# EEPROM_Programmer.net
KiCad netlist of a schematic drawn in EAGLE
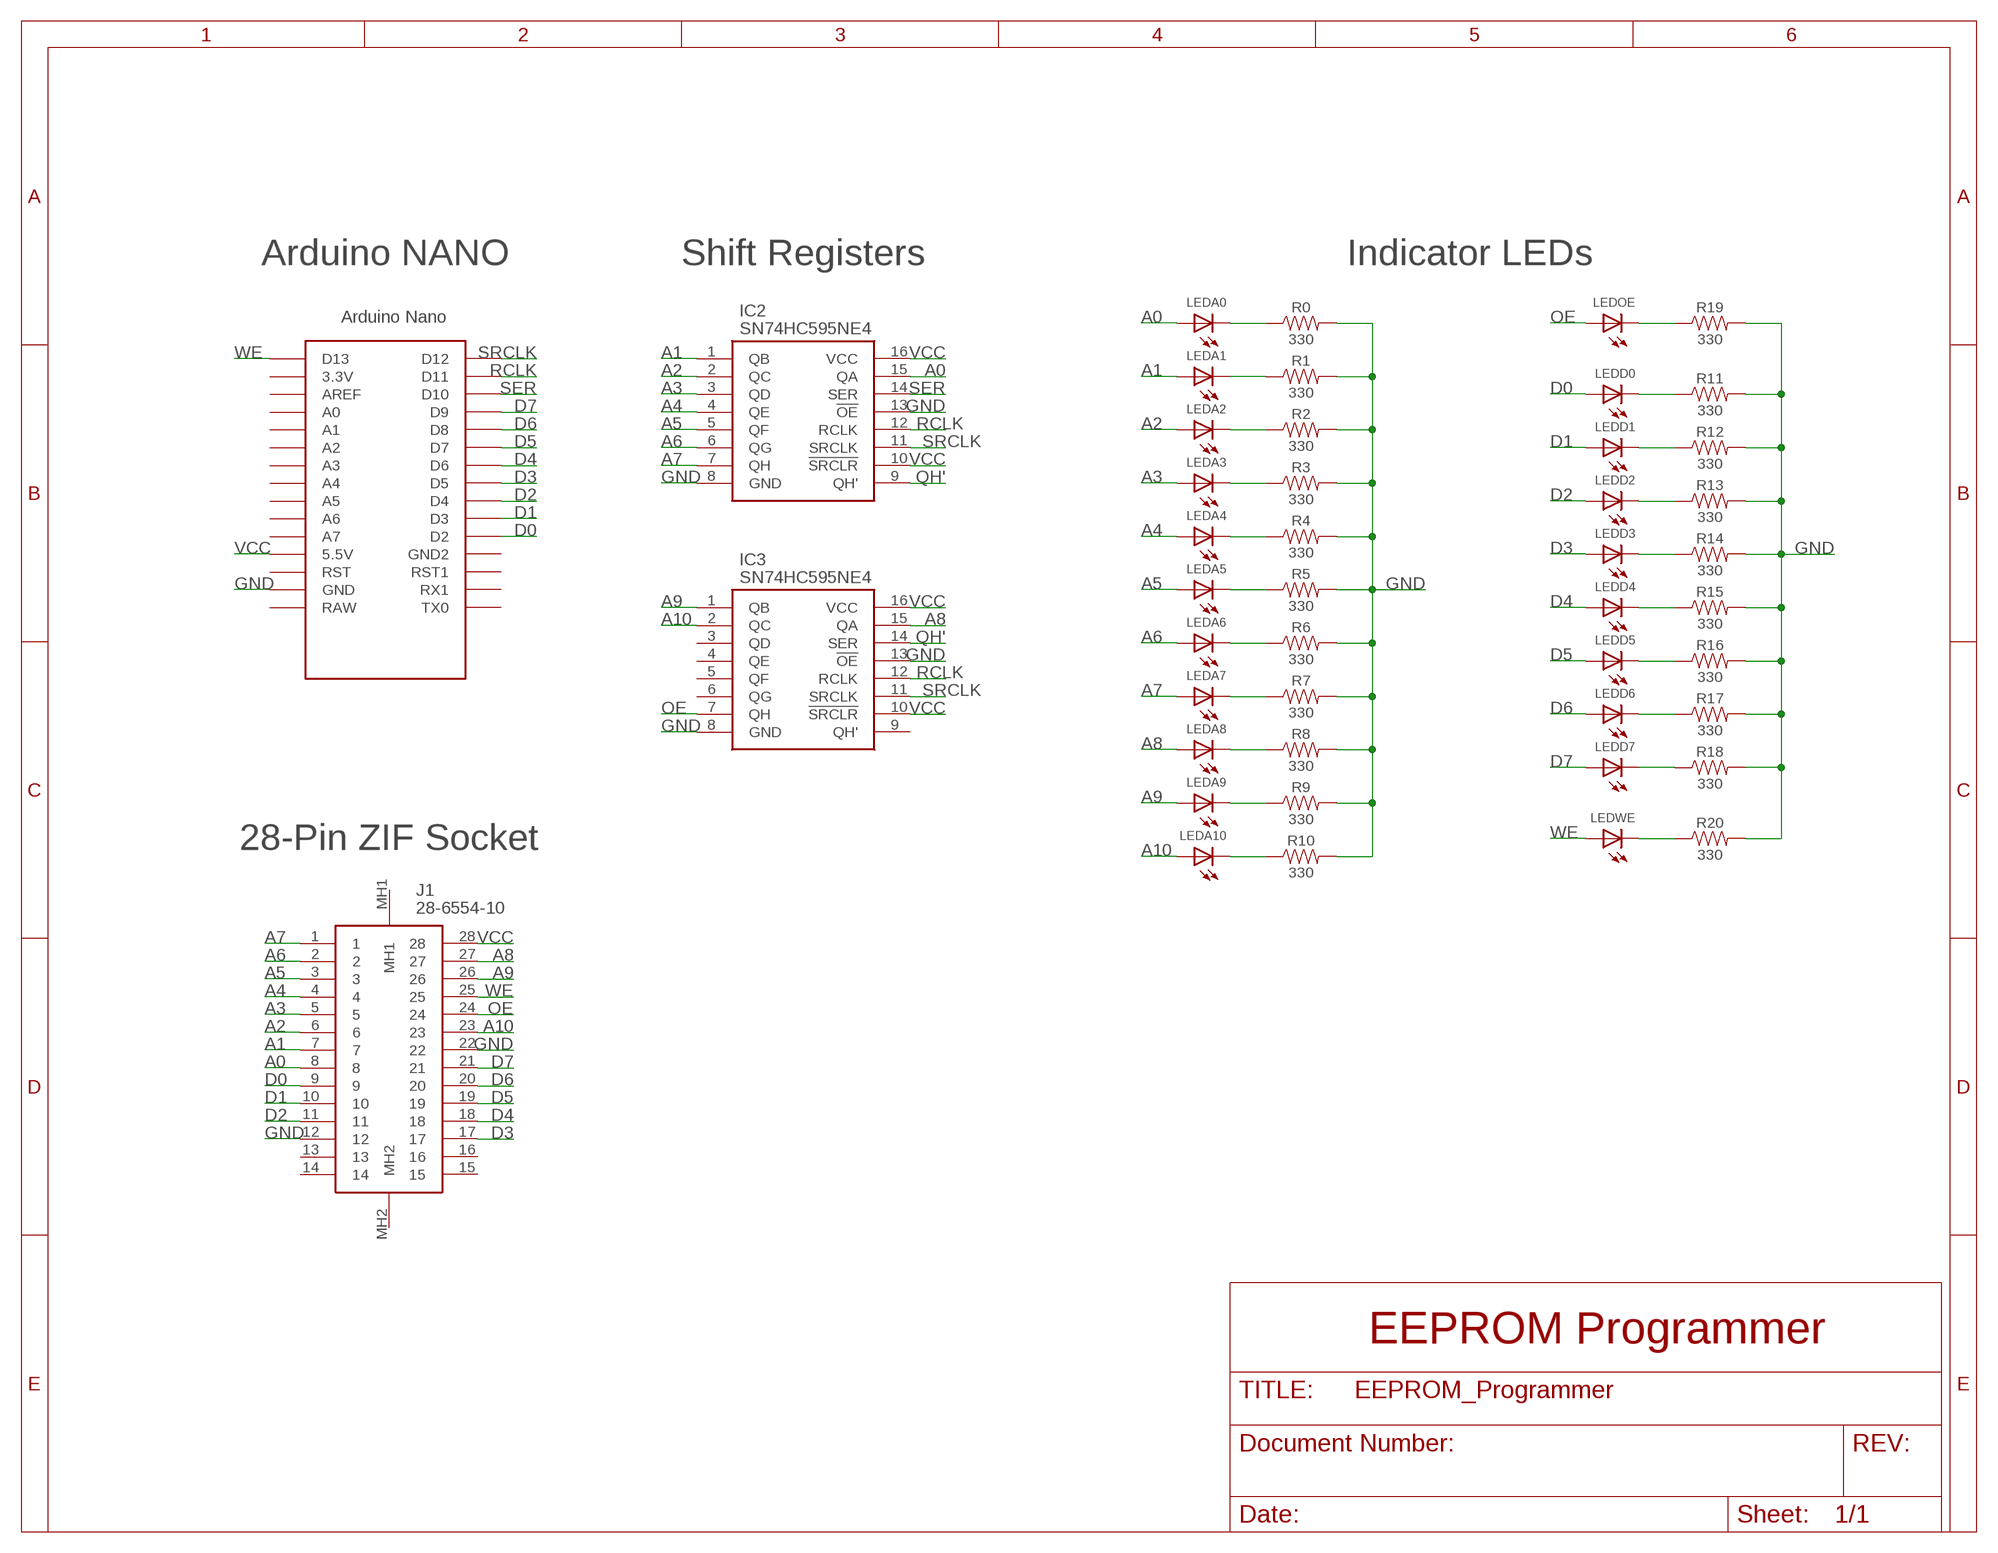
[diagram p0: schematic, sheet 1]

(export (version "E")
  (design (tool "Eeschema 10.0.6"))
  (components
    (comp (ref "IC2")
      (value "SN74HC595NE4")
      (footprint "eagle-import:DIP794W53P254L1930H508Q16N")
      (fields (field (name "MOUSER_PART_NUMBER") "595-SN74HC595NE4"))
      (libsource (lib "eagle-import") (part "SN74HC595NE4"))
    )
    (comp (ref "IC3")
      (value "SN74HC595NE4")
      (footprint "eagle-import:DIP794W53P254L1930H508Q16N")
      (fields (field (name "MOUSER_PART_NUMBER") "595-SN74HC595NE4"))
      (libsource (lib "eagle-import") (part "SN74HC595NE4"))
    )
    (comp (ref "J1")
      (value "28-6554-10")
      (footprint "eagle-import:28655410")
      (fields (field (name "MOUSER_PART_NUMBER") "535-28-6554-10") (field (name "RS_PART_NUMBER") "0403825"))
      (libsource (lib "eagle-import") (part "28-6554-10"))
    )
    (comp (ref "LEDA0")
      (value "LEDCHIPLED_1206")
      (footprint "eagle-import:CHIPLED_1206")
      (libsource (lib "eagle-import") (part "LEDCHIPLED_1206"))
    )
    (comp (ref "LEDA1")
      (value "LEDCHIPLED_1206")
      (footprint "eagle-import:CHIPLED_1206")
      (libsource (lib "eagle-import") (part "LEDCHIPLED_1206"))
    )
    (comp (ref "LEDA2")
      (value "LEDCHIPLED_1206")
      (footprint "eagle-import:CHIPLED_1206")
      (libsource (lib "eagle-import") (part "LEDCHIPLED_1206"))
    )
    (comp (ref "LEDA3")
      (value "LEDCHIPLED_1206")
      (footprint "eagle-import:CHIPLED_1206")
      (libsource (lib "eagle-import") (part "LEDCHIPLED_1206"))
    )
    (comp (ref "LEDA4")
      (value "LEDCHIPLED_1206")
      (footprint "eagle-import:CHIPLED_1206")
      (libsource (lib "eagle-import") (part "LEDCHIPLED_1206"))
    )
    (comp (ref "LEDA5")
      (value "LEDCHIPLED_1206")
      (footprint "eagle-import:CHIPLED_1206")
      (libsource (lib "eagle-import") (part "LEDCHIPLED_1206"))
    )
    (comp (ref "LEDA6")
      (value "LEDCHIPLED_1206")
      (footprint "eagle-import:CHIPLED_1206")
      (libsource (lib "eagle-import") (part "LEDCHIPLED_1206"))
    )
    (comp (ref "LEDA7")
      (value "LEDCHIPLED_1206")
      (footprint "eagle-import:CHIPLED_1206")
      (libsource (lib "eagle-import") (part "LEDCHIPLED_1206"))
    )
    (comp (ref "LEDA8")
      (value "LEDCHIPLED_1206")
      (footprint "eagle-import:CHIPLED_1206")
      (libsource (lib "eagle-import") (part "LEDCHIPLED_1206"))
    )
    (comp (ref "LEDA9")
      (value "LEDCHIPLED_1206")
      (footprint "eagle-import:CHIPLED_1206")
      (libsource (lib "eagle-import") (part "LEDCHIPLED_1206"))
    )
    (comp (ref "LEDA10")
      (value "LEDCHIPLED_1206")
      (footprint "eagle-import:CHIPLED_1206")
      (libsource (lib "eagle-import") (part "LEDCHIPLED_1206"))
    )
    (comp (ref "LEDD0")
      (value "LEDCHIPLED_1206")
      (footprint "eagle-import:CHIPLED_1206")
      (libsource (lib "eagle-import") (part "LEDCHIPLED_1206"))
    )
    (comp (ref "LEDD1")
      (value "LEDCHIPLED_1206")
      (footprint "eagle-import:CHIPLED_1206")
      (libsource (lib "eagle-import") (part "LEDCHIPLED_1206"))
    )
    (comp (ref "LEDD2")
      (value "LEDCHIPLED_1206")
      (footprint "eagle-import:CHIPLED_1206")
      (libsource (lib "eagle-import") (part "LEDCHIPLED_1206"))
    )
    (comp (ref "LEDD3")
      (value "LEDCHIPLED_1206")
      (footprint "eagle-import:CHIPLED_1206")
      (libsource (lib "eagle-import") (part "LEDCHIPLED_1206"))
    )
    (comp (ref "LEDD4")
      (value "LEDCHIPLED_1206")
      (footprint "eagle-import:CHIPLED_1206")
      (libsource (lib "eagle-import") (part "LEDCHIPLED_1206"))
    )
    (comp (ref "LEDD5")
      (value "LEDCHIPLED_1206")
      (footprint "eagle-import:CHIPLED_1206")
      (libsource (lib "eagle-import") (part "LEDCHIPLED_1206"))
    )
    (comp (ref "LEDD6")
      (value "LEDCHIPLED_1206")
      (footprint "eagle-import:CHIPLED_1206")
      (libsource (lib "eagle-import") (part "LEDCHIPLED_1206"))
    )
    (comp (ref "LEDD7")
      (value "LEDCHIPLED_1206")
      (footprint "eagle-import:CHIPLED_1206")
      (libsource (lib "eagle-import") (part "LEDCHIPLED_1206"))
    )
    (comp (ref "LEDOE")
      (value "LEDCHIPLED_1206")
      (footprint "eagle-import:CHIPLED_1206")
      (libsource (lib "eagle-import") (part "LEDCHIPLED_1206"))
    )
    (comp (ref "LEDWE")
      (value "LEDCHIPLED_1206")
      (footprint "eagle-import:CHIPLED_1206")
      (libsource (lib "eagle-import") (part "LEDCHIPLED_1206"))
    )
    (comp (ref "R0")
      (value "330")
      (footprint "eagle-import:1206")
      (libsource (lib "eagle-import") (part "RESISTOR1206"))
    )
    (comp (ref "R1")
      (value "330")
      (footprint "eagle-import:1206")
      (libsource (lib "eagle-import") (part "RESISTOR1206"))
    )
    (comp (ref "R2")
      (value "330")
      (footprint "eagle-import:1206")
      (libsource (lib "eagle-import") (part "RESISTOR1206"))
    )
    (comp (ref "R3")
      (value "330")
      (footprint "eagle-import:1206")
      (libsource (lib "eagle-import") (part "RESISTOR1206"))
    )
    (comp (ref "R4")
      (value "330")
      (footprint "eagle-import:1206")
      (libsource (lib "eagle-import") (part "RESISTOR1206"))
    )
    (comp (ref "R5")
      (value "330")
      (footprint "eagle-import:1206")
      (libsource (lib "eagle-import") (part "RESISTOR1206"))
    )
    (comp (ref "R6")
      (value "330")
      (footprint "eagle-import:1206")
      (libsource (lib "eagle-import") (part "RESISTOR1206"))
    )
    (comp (ref "R7")
      (value "330")
      (footprint "eagle-import:1206")
      (libsource (lib "eagle-import") (part "RESISTOR1206"))
    )
    (comp (ref "R8")
      (value "330")
      (footprint "eagle-import:1206")
      (libsource (lib "eagle-import") (part "RESISTOR1206"))
    )
    (comp (ref "R9")
      (value "330")
      (footprint "eagle-import:1206")
      (libsource (lib "eagle-import") (part "RESISTOR1206"))
    )
    (comp (ref "R10")
      (value "330")
      (footprint "eagle-import:1206")
      (libsource (lib "eagle-import") (part "RESISTOR1206"))
    )
    (comp (ref "R11")
      (value "330")
      (footprint "eagle-import:1206")
      (libsource (lib "eagle-import") (part "RESISTOR1206"))
    )
    (comp (ref "R12")
      (value "330")
      (footprint "eagle-import:1206")
      (libsource (lib "eagle-import") (part "RESISTOR1206"))
    )
    (comp (ref "R13")
      (value "330")
      (footprint "eagle-import:1206")
      (libsource (lib "eagle-import") (part "RESISTOR1206"))
    )
    (comp (ref "R14")
      (value "330")
      (footprint "eagle-import:1206")
      (libsource (lib "eagle-import") (part "RESISTOR1206"))
    )
    (comp (ref "R15")
      (value "330")
      (footprint "eagle-import:1206")
      (libsource (lib "eagle-import") (part "RESISTOR1206"))
    )
    (comp (ref "R16")
      (value "330")
      (footprint "eagle-import:1206")
      (libsource (lib "eagle-import") (part "RESISTOR1206"))
    )
    (comp (ref "R17")
      (value "330")
      (footprint "eagle-import:1206")
      (libsource (lib "eagle-import") (part "RESISTOR1206"))
    )
    (comp (ref "R18")
      (value "330")
      (footprint "eagle-import:1206")
      (libsource (lib "eagle-import") (part "RESISTOR1206"))
    )
    (comp (ref "R19")
      (value "330")
      (footprint "eagle-import:1206")
      (libsource (lib "eagle-import") (part "RESISTOR1206"))
    )
    (comp (ref "R20")
      (value "330")
      (footprint "eagle-import:1206")
      (libsource (lib "eagle-import") (part "RESISTOR1206"))
    )
    (comp (ref "U$1")
      (value "NANO")
      (footprint "eagle-import:NANO")
      (libsource (lib "eagle-import") (part "NANO"))
    )
  )
  (nets
    (net (code "1") (name "/A0") (class "Default")
      (node (ref "IC2") (pin "15") (pinfunction "QA_15") (pintype "bidirectional"))
      (node (ref "J1") (pin "8") (pinfunction "8_8") (pintype "bidirectional"))
      (node (ref "LEDA0") (pin "A") (pinfunction "A_A") (pintype "passive"))
    )
    (net (code "2") (name "/A1") (class "Default")
      (node (ref "IC2") (pin "1") (pinfunction "QB_1") (pintype "bidirectional"))
      (node (ref "J1") (pin "7") (pinfunction "7_7") (pintype "bidirectional"))
      (node (ref "LEDA1") (pin "A") (pinfunction "A_A") (pintype "passive"))
    )
    (net (code "3") (name "/A2") (class "Default")
      (node (ref "IC2") (pin "2") (pinfunction "QC_2") (pintype "bidirectional"))
      (node (ref "J1") (pin "6") (pinfunction "6_6") (pintype "bidirectional"))
      (node (ref "LEDA2") (pin "A") (pinfunction "A_A") (pintype "passive"))
    )
    (net (code "4") (name "/A3") (class "Default")
      (node (ref "IC2") (pin "3") (pinfunction "QD_3") (pintype "bidirectional"))
      (node (ref "J1") (pin "5") (pinfunction "5_5") (pintype "bidirectional"))
      (node (ref "LEDA3") (pin "A") (pinfunction "A_A") (pintype "passive"))
    )
    (net (code "5") (name "/A4") (class "Default")
      (node (ref "IC2") (pin "4") (pinfunction "QE_4") (pintype "bidirectional"))
      (node (ref "J1") (pin "4") (pinfunction "4_4") (pintype "bidirectional"))
      (node (ref "LEDA4") (pin "A") (pinfunction "A_A") (pintype "passive"))
    )
    (net (code "6") (name "/A5") (class "Default")
      (node (ref "IC2") (pin "5") (pinfunction "QF_5") (pintype "bidirectional"))
      (node (ref "J1") (pin "3") (pinfunction "3_3") (pintype "bidirectional"))
      (node (ref "LEDA5") (pin "A") (pinfunction "A_A") (pintype "passive"))
    )
    (net (code "7") (name "/A6") (class "Default")
      (node (ref "IC2") (pin "6") (pinfunction "QG_6") (pintype "bidirectional"))
      (node (ref "J1") (pin "2") (pinfunction "2_2") (pintype "bidirectional"))
      (node (ref "LEDA6") (pin "A") (pinfunction "A_A") (pintype "passive"))
    )
    (net (code "8") (name "/A7") (class "Default")
      (node (ref "IC2") (pin "7") (pinfunction "QH_7") (pintype "bidirectional"))
      (node (ref "J1") (pin "1") (pinfunction "1_1") (pintype "bidirectional"))
      (node (ref "LEDA7") (pin "A") (pinfunction "A_A") (pintype "passive"))
    )
    (net (code "9") (name "/A8") (class "Default")
      (node (ref "IC3") (pin "15") (pinfunction "QA_15") (pintype "bidirectional"))
      (node (ref "J1") (pin "27") (pinfunction "27_27") (pintype "bidirectional"))
      (node (ref "LEDA8") (pin "A") (pinfunction "A_A") (pintype "passive"))
    )
    (net (code "10") (name "/A9") (class "Default")
      (node (ref "IC3") (pin "1") (pinfunction "QB_1") (pintype "bidirectional"))
      (node (ref "J1") (pin "26") (pinfunction "26_26") (pintype "bidirectional"))
      (node (ref "LEDA9") (pin "A") (pinfunction "A_A") (pintype "passive"))
    )
    (net (code "11") (name "/A10") (class "Default")
      (node (ref "IC3") (pin "2") (pinfunction "QC_2") (pintype "bidirectional"))
      (node (ref "J1") (pin "23") (pinfunction "23_23") (pintype "bidirectional"))
      (node (ref "LEDA10") (pin "A") (pinfunction "A_A") (pintype "passive"))
    )
    (net (code "12") (name "/D0") (class "Default")
      (node (ref "J1") (pin "9") (pinfunction "9_9") (pintype "bidirectional"))
      (node (ref "LEDD0") (pin "A") (pinfunction "A_A") (pintype "passive"))
      (node (ref "U$1") (pin "D2") (pinfunction "D2_D2") (pintype "bidirectional"))
    )
    (net (code "13") (name "/D1") (class "Default")
      (node (ref "J1") (pin "10") (pinfunction "10_10") (pintype "bidirectional"))
      (node (ref "LEDD1") (pin "A") (pinfunction "A_A") (pintype "passive"))
      (node (ref "U$1") (pin "D3") (pinfunction "D3_D3") (pintype "bidirectional"))
    )
    (net (code "14") (name "/D2") (class "Default")
      (node (ref "J1") (pin "11") (pinfunction "11_11") (pintype "bidirectional"))
      (node (ref "LEDD2") (pin "A") (pinfunction "A_A") (pintype "passive"))
      (node (ref "U$1") (pin "D4") (pinfunction "D4_D4") (pintype "bidirectional"))
    )
    (net (code "15") (name "/D3") (class "Default")
      (node (ref "J1") (pin "17") (pinfunction "17_17") (pintype "bidirectional"))
      (node (ref "LEDD3") (pin "A") (pinfunction "A_A") (pintype "passive"))
      (node (ref "U$1") (pin "D5") (pinfunction "D5_D5") (pintype "bidirectional"))
    )
    (net (code "16") (name "/D4") (class "Default")
      (node (ref "J1") (pin "18") (pinfunction "18_18") (pintype "bidirectional"))
      (node (ref "LEDD4") (pin "A") (pinfunction "A_A") (pintype "passive"))
      (node (ref "U$1") (pin "D6") (pinfunction "D6_D6") (pintype "bidirectional"))
    )
    (net (code "17") (name "/D5") (class "Default")
      (node (ref "J1") (pin "19") (pinfunction "19_19") (pintype "bidirectional"))
      (node (ref "LEDD5") (pin "A") (pinfunction "A_A") (pintype "passive"))
      (node (ref "U$1") (pin "D7") (pinfunction "D7_D7") (pintype "bidirectional"))
    )
    (net (code "18") (name "/D6") (class "Default")
      (node (ref "J1") (pin "20") (pinfunction "20_20") (pintype "bidirectional"))
      (node (ref "LEDD6") (pin "A") (pinfunction "A_A") (pintype "passive"))
      (node (ref "U$1") (pin "D8") (pinfunction "D8_D8") (pintype "bidirectional"))
    )
    (net (code "19") (name "/D7") (class "Default")
      (node (ref "J1") (pin "21") (pinfunction "21_21") (pintype "bidirectional"))
      (node (ref "LEDD7") (pin "A") (pinfunction "A_A") (pintype "passive"))
      (node (ref "U$1") (pin "D9") (pinfunction "D9_D9") (pintype "bidirectional"))
    )
    (net (code "20") (name "/GND") (class "Default")
      (node (ref "IC2") (pin "13") (pinfunction "~{OE}_13") (pintype "bidirectional"))
      (node (ref "IC2") (pin "8") (pinfunction "GND_8") (pintype "bidirectional"))
      (node (ref "IC3") (pin "13") (pinfunction "~{OE}_13") (pintype "bidirectional"))
      (node (ref "IC3") (pin "8") (pinfunction "GND_8") (pintype "bidirectional"))
      (node (ref "J1") (pin "12") (pinfunction "12_12") (pintype "bidirectional"))
      (node (ref "J1") (pin "22") (pinfunction "22_22") (pintype "bidirectional"))
      (node (ref "R0") (pin "2") (pinfunction "2_2") (pintype "passive"))
      (node (ref "R1") (pin "2") (pinfunction "2_2") (pintype "passive"))
      (node (ref "R10") (pin "2") (pinfunction "2_2") (pintype "passive"))
      (node (ref "R11") (pin "2") (pinfunction "2_2") (pintype "passive"))
      (node (ref "R12") (pin "2") (pinfunction "2_2") (pintype "passive"))
      (node (ref "R13") (pin "2") (pinfunction "2_2") (pintype "passive"))
      (node (ref "R14") (pin "2") (pinfunction "2_2") (pintype "passive"))
      (node (ref "R15") (pin "2") (pinfunction "2_2") (pintype "passive"))
      (node (ref "R16") (pin "2") (pinfunction "2_2") (pintype "passive"))
      (node (ref "R17") (pin "2") (pinfunction "2_2") (pintype "passive"))
      (node (ref "R18") (pin "2") (pinfunction "2_2") (pintype "passive"))
      (node (ref "R19") (pin "2") (pinfunction "2_2") (pintype "passive"))
      (node (ref "R2") (pin "2") (pinfunction "2_2") (pintype "passive"))
      (node (ref "R20") (pin "2") (pinfunction "2_2") (pintype "passive"))
      (node (ref "R3") (pin "2") (pinfunction "2_2") (pintype "passive"))
      (node (ref "R4") (pin "2") (pinfunction "2_2") (pintype "passive"))
      (node (ref "R5") (pin "2") (pinfunction "2_2") (pintype "passive"))
      (node (ref "R6") (pin "2") (pinfunction "2_2") (pintype "passive"))
      (node (ref "R7") (pin "2") (pinfunction "2_2") (pintype "passive"))
      (node (ref "R8") (pin "2") (pinfunction "2_2") (pintype "passive"))
      (node (ref "R9") (pin "2") (pinfunction "2_2") (pintype "passive"))
      (node (ref "U$1") (pin "GND") (pinfunction "GND_GND") (pintype "bidirectional"))
    )
    (net (code "21") (name "/OE") (class "Default")
      (node (ref "IC3") (pin "7") (pinfunction "QH_7") (pintype "bidirectional"))
      (node (ref "J1") (pin "24") (pinfunction "24_24") (pintype "bidirectional"))
      (node (ref "LEDOE") (pin "A") (pinfunction "A_A") (pintype "passive"))
    )
    (net (code "22") (name "/QH'") (class "Default")
      (node (ref "IC2") (pin "9") (pinfunction "QH'_9") (pintype "bidirectional"))
      (node (ref "IC3") (pin "14") (pinfunction "SER_14") (pintype "bidirectional"))
    )
    (net (code "23") (name "/RCLK") (class "Default")
      (node (ref "IC2") (pin "12") (pinfunction "RCLK_12") (pintype "bidirectional"))
      (node (ref "IC3") (pin "12") (pinfunction "RCLK_12") (pintype "bidirectional"))
      (node (ref "U$1") (pin "D11") (pinfunction "D11_D11") (pintype "bidirectional"))
    )
    (net (code "24") (name "/SER") (class "Default")
      (node (ref "IC2") (pin "14") (pinfunction "SER_14") (pintype "bidirectional"))
      (node (ref "U$1") (pin "D10") (pinfunction "D10_D10") (pintype "bidirectional"))
    )
    (net (code "25") (name "/SRCLK") (class "Default")
      (node (ref "IC2") (pin "11") (pinfunction "SRCLK_11") (pintype "bidirectional"))
      (node (ref "IC3") (pin "11") (pinfunction "SRCLK_11") (pintype "bidirectional"))
      (node (ref "U$1") (pin "D12") (pinfunction "D12_D12") (pintype "bidirectional"))
    )
    (net (code "26") (name "/VCC") (class "Default")
      (node (ref "IC2") (pin "10") (pinfunction "~{SRCLR}_10") (pintype "bidirectional"))
      (node (ref "IC2") (pin "16") (pinfunction "VCC_16") (pintype "bidirectional"))
      (node (ref "IC3") (pin "10") (pinfunction "~{SRCLR}_10") (pintype "bidirectional"))
      (node (ref "IC3") (pin "16") (pinfunction "VCC_16") (pintype "bidirectional"))
      (node (ref "J1") (pin "28") (pinfunction "28_28") (pintype "bidirectional"))
      (node (ref "U$1") (pin "5V") (pinfunction "5.5V_5V") (pintype "bidirectional"))
    )
    (net (code "27") (name "/WE") (class "Default")
      (node (ref "J1") (pin "25") (pinfunction "25_25") (pintype "bidirectional"))
      (node (ref "LEDWE") (pin "A") (pinfunction "A_A") (pintype "passive"))
      (node (ref "U$1") (pin "D13") (pinfunction "D13_D13") (pintype "bidirectional"))
    )
    (net (code "28") (name "Net-(LEDA0-PadC)") (class "Default")
      (node (ref "LEDA0") (pin "C") (pinfunction "C_C") (pintype "passive"))
      (node (ref "R0") (pin "1") (pinfunction "1_1") (pintype "passive"))
    )
    (net (code "29") (name "Net-(LEDA1-PadC)") (class "Default")
      (node (ref "LEDA1") (pin "C") (pinfunction "C_C") (pintype "passive"))
      (node (ref "R1") (pin "1") (pinfunction "1_1") (pintype "passive"))
    )
    (net (code "30") (name "Net-(LEDA2-PadC)") (class "Default")
      (node (ref "LEDA2") (pin "C") (pinfunction "C_C") (pintype "passive"))
      (node (ref "R2") (pin "1") (pinfunction "1_1") (pintype "passive"))
    )
    (net (code "31") (name "Net-(LEDA3-PadC)") (class "Default")
      (node (ref "LEDA3") (pin "C") (pinfunction "C_C") (pintype "passive"))
      (node (ref "R3") (pin "1") (pinfunction "1_1") (pintype "passive"))
    )
    (net (code "32") (name "Net-(LEDA4-PadC)") (class "Default")
      (node (ref "LEDA4") (pin "C") (pinfunction "C_C") (pintype "passive"))
      (node (ref "R4") (pin "1") (pinfunction "1_1") (pintype "passive"))
    )
    (net (code "33") (name "Net-(LEDA5-PadC)") (class "Default")
      (node (ref "LEDA5") (pin "C") (pinfunction "C_C") (pintype "passive"))
      (node (ref "R5") (pin "1") (pinfunction "1_1") (pintype "passive"))
    )
    (net (code "34") (name "Net-(LEDA6-PadC)") (class "Default")
      (node (ref "LEDA6") (pin "C") (pinfunction "C_C") (pintype "passive"))
      (node (ref "R6") (pin "1") (pinfunction "1_1") (pintype "passive"))
    )
    (net (code "35") (name "Net-(LEDA7-PadC)") (class "Default")
      (node (ref "LEDA7") (pin "C") (pinfunction "C_C") (pintype "passive"))
      (node (ref "R7") (pin "1") (pinfunction "1_1") (pintype "passive"))
    )
    (net (code "36") (name "Net-(LEDA8-PadC)") (class "Default")
      (node (ref "LEDA8") (pin "C") (pinfunction "C_C") (pintype "passive"))
      (node (ref "R8") (pin "1") (pinfunction "1_1") (pintype "passive"))
    )
    (net (code "37") (name "Net-(LEDA9-PadC)") (class "Default")
      (node (ref "LEDA9") (pin "C") (pinfunction "C_C") (pintype "passive"))
      (node (ref "R9") (pin "1") (pinfunction "1_1") (pintype "passive"))
    )
    (net (code "38") (name "Net-(LEDA10-PadC)") (class "Default")
      (node (ref "LEDA10") (pin "C") (pinfunction "C_C") (pintype "passive"))
      (node (ref "R10") (pin "1") (pinfunction "1_1") (pintype "passive"))
    )
    (net (code "39") (name "Net-(LEDD0-PadC)") (class "Default")
      (node (ref "LEDD0") (pin "C") (pinfunction "C_C") (pintype "passive"))
      (node (ref "R11") (pin "1") (pinfunction "1_1") (pintype "passive"))
    )
    (net (code "40") (name "Net-(LEDD1-PadC)") (class "Default")
      (node (ref "LEDD1") (pin "C") (pinfunction "C_C") (pintype "passive"))
      (node (ref "R12") (pin "1") (pinfunction "1_1") (pintype "passive"))
    )
    (net (code "41") (name "Net-(LEDD2-PadC)") (class "Default")
      (node (ref "LEDD2") (pin "C") (pinfunction "C_C") (pintype "passive"))
      (node (ref "R13") (pin "1") (pinfunction "1_1") (pintype "passive"))
    )
    (net (code "42") (name "Net-(LEDD3-PadC)") (class "Default")
      (node (ref "LEDD3") (pin "C") (pinfunction "C_C") (pintype "passive"))
      (node (ref "R14") (pin "1") (pinfunction "1_1") (pintype "passive"))
    )
    (net (code "43") (name "Net-(LEDD4-PadC)") (class "Default")
      (node (ref "LEDD4") (pin "C") (pinfunction "C_C") (pintype "passive"))
      (node (ref "R15") (pin "1") (pinfunction "1_1") (pintype "passive"))
    )
    (net (code "44") (name "Net-(LEDD5-PadC)") (class "Default")
      (node (ref "LEDD5") (pin "C") (pinfunction "C_C") (pintype "passive"))
      (node (ref "R16") (pin "1") (pinfunction "1_1") (pintype "passive"))
    )
    (net (code "45") (name "Net-(LEDD6-PadC)") (class "Default")
      (node (ref "LEDD6") (pin "C") (pinfunction "C_C") (pintype "passive"))
      (node (ref "R17") (pin "1") (pinfunction "1_1") (pintype "passive"))
    )
    (net (code "46") (name "Net-(LEDD7-PadC)") (class "Default")
      (node (ref "LEDD7") (pin "C") (pinfunction "C_C") (pintype "passive"))
      (node (ref "R18") (pin "1") (pinfunction "1_1") (pintype "passive"))
    )
    (net (code "47") (name "Net-(LEDOE-PadC)") (class "Default")
      (node (ref "LEDOE") (pin "C") (pinfunction "C_C") (pintype "passive"))
      (node (ref "R19") (pin "1") (pinfunction "1_1") (pintype "passive"))
    )
    (net (code "48") (name "Net-(LEDWE-PadC)") (class "Default")
      (node (ref "LEDWE") (pin "C") (pinfunction "C_C") (pintype "passive"))
      (node (ref "R20") (pin "1") (pinfunction "1_1") (pintype "passive"))
    )
    (net (code "49") (name "unconnected-(IC3-QD-Pad3)") (class "Default")
      (node (ref "IC3") (pin "3") (pinfunction "QD_3") (pintype "bidirectional"))
    )
    (net (code "50") (name "unconnected-(IC3-QE-Pad4)") (class "Default")
      (node (ref "IC3") (pin "4") (pinfunction "QE_4") (pintype "bidirectional"))
    )
    (net (code "51") (name "unconnected-(IC3-QF-Pad5)") (class "Default")
      (node (ref "IC3") (pin "5") (pinfunction "QF_5") (pintype "bidirectional"))
    )
    (net (code "52") (name "unconnected-(IC3-QG-Pad6)") (class "Default")
      (node (ref "IC3") (pin "6") (pinfunction "QG_6") (pintype "bidirectional"))
    )
    (net (code "53") (name "unconnected-(IC3-QH'-Pad9)") (class "Default")
      (node (ref "IC3") (pin "9") (pinfunction "QH'_9") (pintype "bidirectional"))
    )
    (net (code "54") (name "unconnected-(J1-Pad13)") (class "Default")
      (node (ref "J1") (pin "13") (pinfunction "13_13") (pintype "bidirectional"))
    )
    (net (code "55") (name "unconnected-(J1-Pad14)") (class "Default")
      (node (ref "J1") (pin "14") (pinfunction "14_14") (pintype "bidirectional"))
    )
    (net (code "56") (name "unconnected-(J1-Pad15)") (class "Default")
      (node (ref "J1") (pin "15") (pinfunction "15_15") (pintype "bidirectional"))
    )
    (net (code "57") (name "unconnected-(J1-Pad16)") (class "Default")
      (node (ref "J1") (pin "16") (pinfunction "16_16") (pintype "bidirectional"))
    )
    (net (code "58") (name "unconnected-(J1-PadMH1)") (class "Default")
      (node (ref "J1") (pin "MH1") (pinfunction "MH1_MH1") (pintype "bidirectional"))
    )
    (net (code "59") (name "unconnected-(J1-PadMH2)") (class "Default")
      (node (ref "J1") (pin "MH2") (pinfunction "MH2_MH2") (pintype "bidirectional"))
    )
    (net (code "60") (name "unconnected-(U$1-GND2-PadGND1)") (class "Default")
      (node (ref "U$1") (pin "GND1") (pinfunction "GND2_GND1") (pintype "bidirectional"))
    )
    (net (code "61") (name "unconnected-(U$1-Pad3.3V)") (class "Default")
      (node (ref "U$1") (pin "3.3V") (pinfunction "3.3V_3.3V") (pintype "bidirectional"))
    )
    (net (code "62") (name "unconnected-(U$1-PadA0)") (class "Default")
      (node (ref "U$1") (pin "A0") (pinfunction "A0_A0") (pintype "bidirectional"))
    )
    (net (code "63") (name "unconnected-(U$1-PadA1)") (class "Default")
      (node (ref "U$1") (pin "A1") (pinfunction "A1_A1") (pintype "bidirectional"))
    )
    (net (code "64") (name "unconnected-(U$1-PadA2)") (class "Default")
      (node (ref "U$1") (pin "A2") (pinfunction "A2_A2") (pintype "bidirectional"))
    )
    (net (code "65") (name "unconnected-(U$1-PadA3)") (class "Default")
      (node (ref "U$1") (pin "A3") (pinfunction "A3_A3") (pintype "bidirectional"))
    )
    (net (code "66") (name "unconnected-(U$1-PadA4)") (class "Default")
      (node (ref "U$1") (pin "A4") (pinfunction "A4_A4") (pintype "bidirectional"))
    )
    (net (code "67") (name "unconnected-(U$1-PadA5)") (class "Default")
      (node (ref "U$1") (pin "A5") (pinfunction "A5_A5") (pintype "bidirectional"))
    )
    (net (code "68") (name "unconnected-(U$1-PadA6)") (class "Default")
      (node (ref "U$1") (pin "A6") (pinfunction "A6_A6") (pintype "bidirectional"))
    )
    (net (code "69") (name "unconnected-(U$1-PadA7)") (class "Default")
      (node (ref "U$1") (pin "A7") (pinfunction "A7_A7") (pintype "bidirectional"))
    )
    (net (code "70") (name "unconnected-(U$1-PadAREF)") (class "Default")
      (node (ref "U$1") (pin "AREF") (pinfunction "AREF_AREF") (pintype "bidirectional"))
    )
    (net (code "71") (name "unconnected-(U$1-PadRAW)") (class "Default")
      (node (ref "U$1") (pin "RAW") (pinfunction "RAW_RAW") (pintype "bidirectional"))
    )
    (net (code "72") (name "unconnected-(U$1-PadRST)") (class "Default")
      (node (ref "U$1") (pin "RST") (pinfunction "RST_RST") (pintype "bidirectional"))
    )
    (net (code "73") (name "unconnected-(U$1-PadRST1)") (class "Default")
      (node (ref "U$1") (pin "RST1") (pinfunction "RST1_RST1") (pintype "bidirectional"))
    )
    (net (code "74") (name "unconnected-(U$1-PadRX1)") (class "Default")
      (node (ref "U$1") (pin "RX1") (pinfunction "RX1_RX1") (pintype "bidirectional"))
    )
    (net (code "75") (name "unconnected-(U$1-PadTX0)") (class "Default")
      (node (ref "U$1") (pin "TX0") (pinfunction "TX0_TX0") (pintype "bidirectional"))
    )
  )
)
